# ECE_362_mini_project2.net
KiCad netlist of a schematic drawn in EAGLE
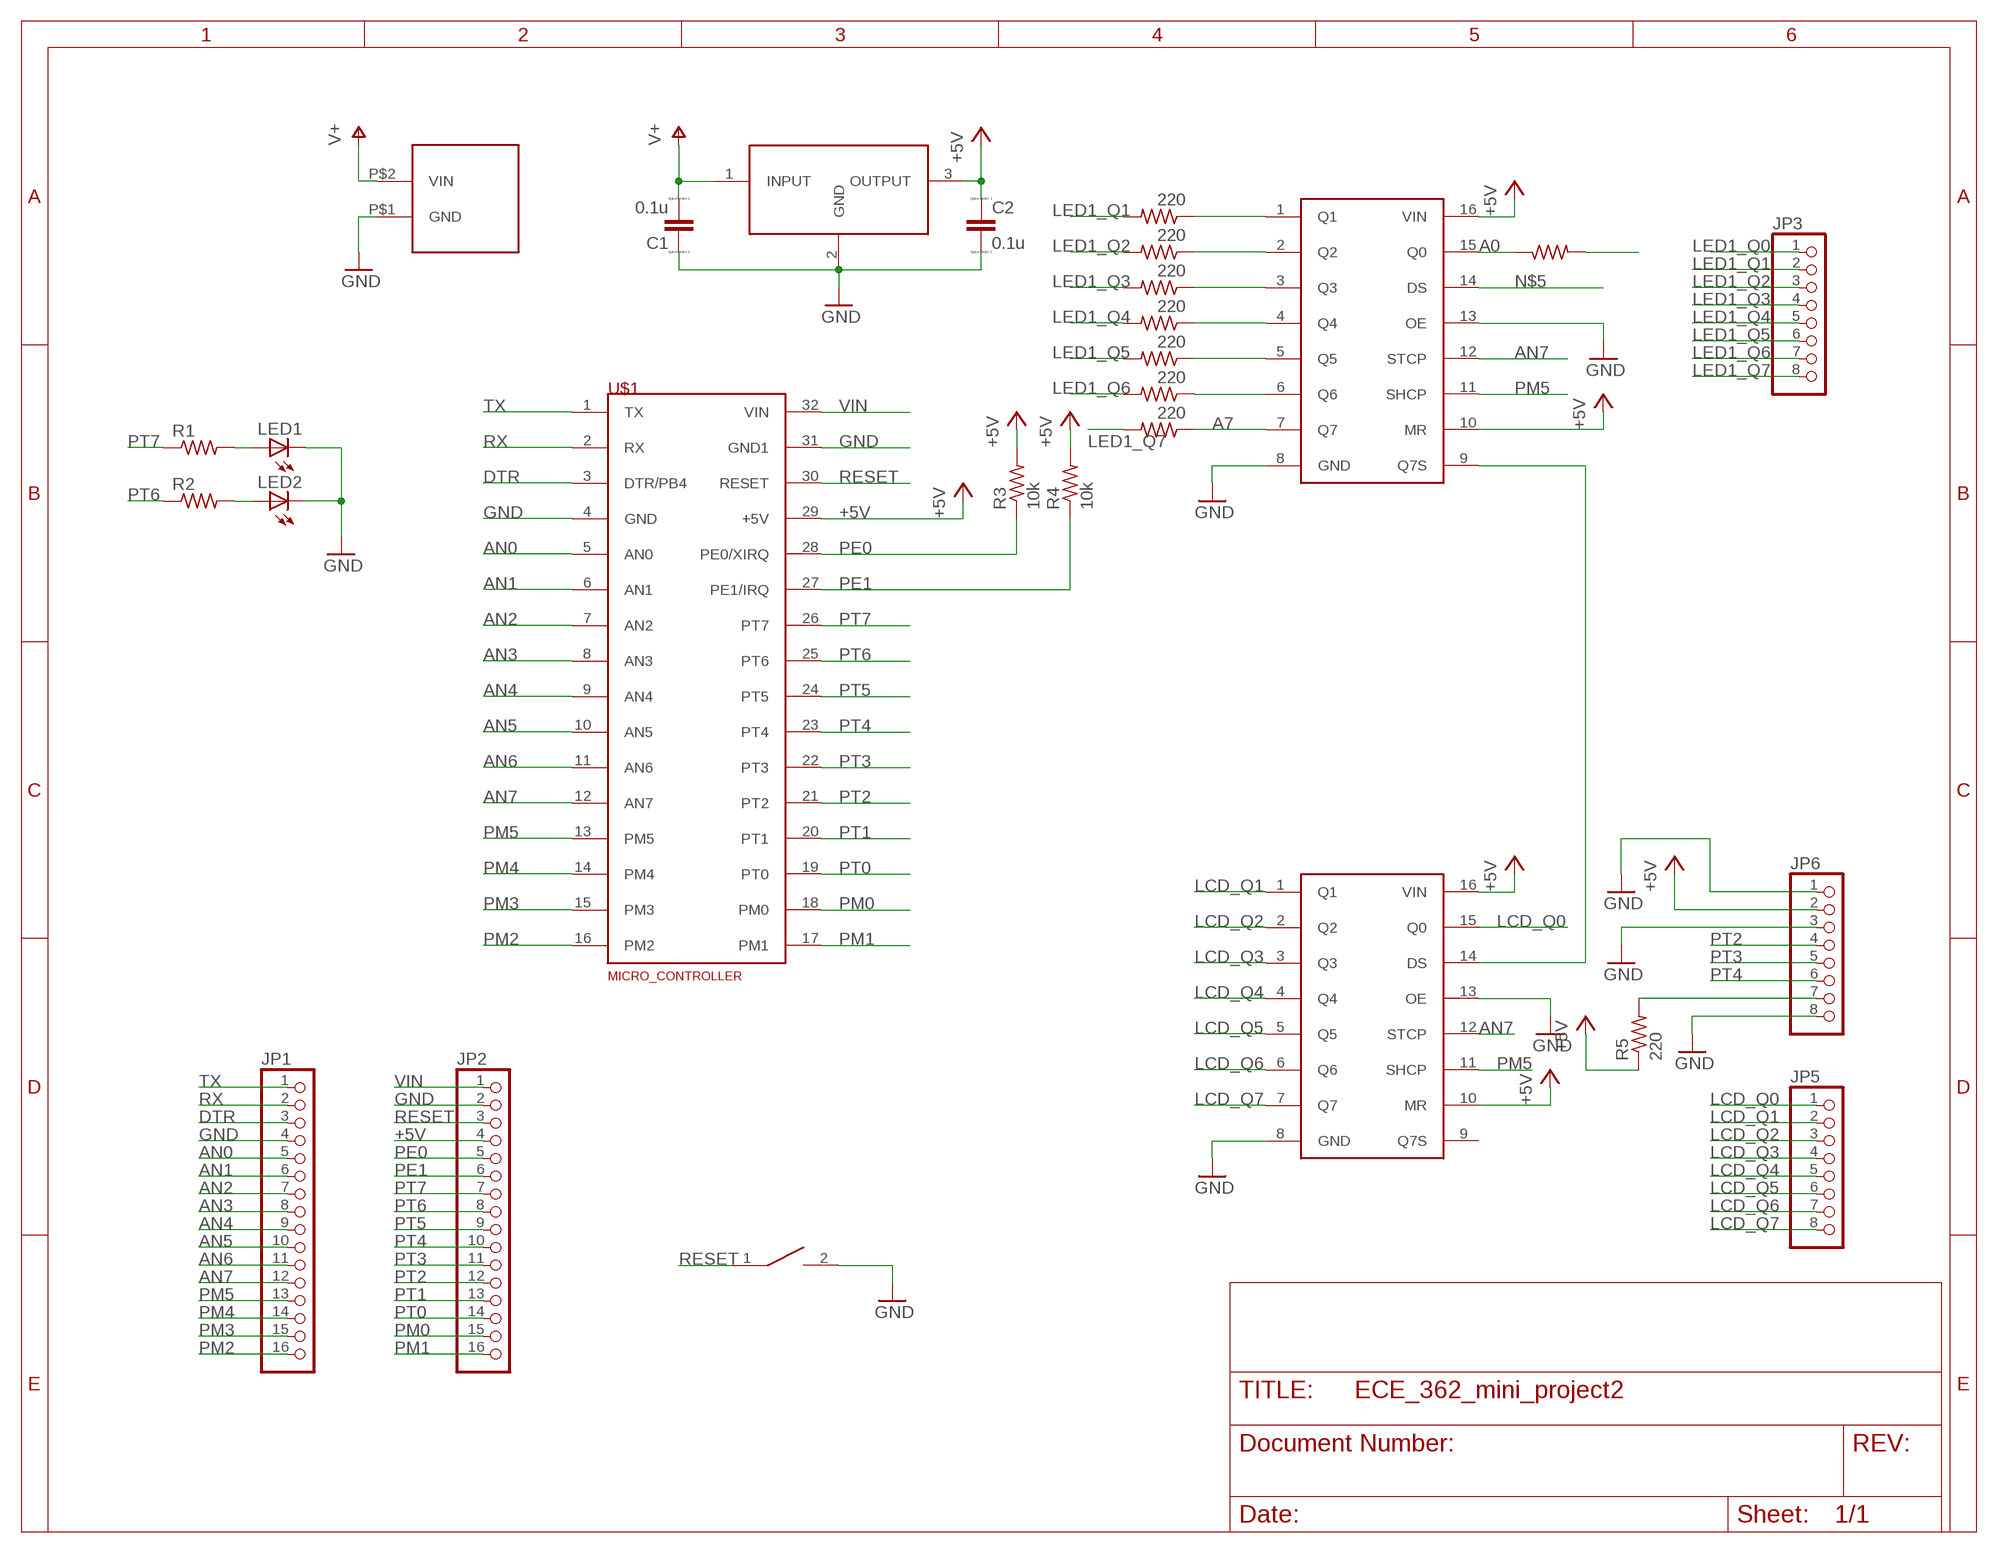
[diagram p0: schematic, sheet 1]

(export (version "E")
  (design (tool "Eeschema 10.0.6"))
  (components
    (comp (ref "BOOT_SW")
      (value "SWITCH")
      (footprint "eagle-import:SW_2512")
      (libsource (lib "eagle-import") (part "SWITCH"))
    )
    (comp (ref "C1")
      (value "0.1u")
      (footprint "eagle-import:C0603")
      (libsource (lib "eagle-import") (part "CC0603"))
    )
    (comp (ref "C2")
      (value "0.1u")
      (footprint "eagle-import:C0603")
      (libsource (lib "eagle-import") (part "CC0603"))
    )
    (comp (ref "JP1")
      (value "PINHD-1X16")
      (footprint "eagle-import:1X16")
      (libsource (lib "eagle-import") (part "PINHD-1X16"))
    )
    (comp (ref "JP2")
      (value "PINHD-1X16")
      (footprint "eagle-import:1X16")
      (libsource (lib "eagle-import") (part "PINHD-1X16"))
    )
    (comp (ref "JP3")
      (value "PINHD-1X8")
      (footprint "eagle-import:1X08")
      (libsource (lib "eagle-import") (part "PINHD-1X8"))
    )
    (comp (ref "JP5")
      (value "PINHD-1X8")
      (footprint "eagle-import:1X08")
      (libsource (lib "eagle-import") (part "PINHD-1X8"))
    )
    (comp (ref "JP6")
      (value "PINHD-1X8")
      (footprint "eagle-import:1X08")
      (libsource (lib "eagle-import") (part "PINHD-1X8"))
    )
    (comp (ref "LED1")
      (value "LEDCHIPLED_0603")
      (footprint "eagle-import:CHIPLED_0603")
      (libsource (lib "eagle-import") (part "LEDCHIPLED_0603"))
    )
    (comp (ref "LED2")
      (value "LEDCHIPLED_0603")
      (footprint "eagle-import:CHIPLED_0603")
      (libsource (lib "eagle-import") (part "LEDCHIPLED_0603"))
    )
    (comp (ref "R1")
      (value "R-US_R0603")
      (footprint "eagle-import:R0603")
      (libsource (lib "eagle-import") (part "R-US_R0603"))
    )
    (comp (ref "R2")
      (value "R-US_R0603")
      (footprint "eagle-import:R0603")
      (libsource (lib "eagle-import") (part "R-US_R0603"))
    )
    (comp (ref "R3")
      (value "10k")
      (footprint "eagle-import:R0603")
      (libsource (lib "eagle-import") (part "R-US_R0603"))
    )
    (comp (ref "R4")
      (value "10k")
      (footprint "eagle-import:R0603")
      (libsource (lib "eagle-import") (part "R-US_R0603"))
    )
    (comp (ref "R5")
      (value "220")
      (footprint "eagle-import:R0603")
      (libsource (lib "eagle-import") (part "R-US_R0603"))
    )
    (comp (ref "R6")
      (value "220")
      (footprint "eagle-import:R0603")
      (libsource (lib "eagle-import") (part "R-US_R0603"))
    )
    (comp (ref "R7")
      (value "220")
      (footprint "eagle-import:R0603")
      (libsource (lib "eagle-import") (part "R-US_R0603"))
    )
    (comp (ref "R8")
      (value "220")
      (footprint "eagle-import:R0603")
      (libsource (lib "eagle-import") (part "R-US_R0603"))
    )
    (comp (ref "R9")
      (value "220")
      (footprint "eagle-import:R0603")
      (libsource (lib "eagle-import") (part "R-US_R0603"))
    )
    (comp (ref "R10")
      (value "220")
      (footprint "eagle-import:R0603")
      (libsource (lib "eagle-import") (part "R-US_R0603"))
    )
    (comp (ref "R11")
      (value "220")
      (footprint "eagle-import:R0603")
      (libsource (lib "eagle-import") (part "R-US_R0603"))
    )
    (comp (ref "R12")
      (value "220")
      (footprint "eagle-import:R0603")
      (libsource (lib "eagle-import") (part "R-US_R0603"))
    )
    (comp (ref "R20")
      (value "220")
      (footprint "eagle-import:R0603")
      (libsource (lib "eagle-import") (part "R-US_R0603"))
    )
    (comp (ref "U$1")
      (value "MICRO_CONTROLLER")
      (footprint "eagle-import:MICRO_CONTROLLER")
      (libsource (lib "eagle-import") (part "MICRO_CONTROLLER"))
    )
    (comp (ref "U$2")
      (value "SHIFT_REGISTER")
      (footprint "eagle-import:N5")
      (libsource (lib "eagle-import") (part "SHIFT_REGISTER"))
    )
    (comp (ref "U$3")
      (value "XT60")
      (footprint "eagle-import:XT60")
      (libsource (lib "eagle-import") (part "XT60"))
    )
    (comp (ref "U$5")
      (value "SHIFT_REGISTER")
      (footprint "eagle-import:N5")
      (libsource (lib "eagle-import") (part "SHIFT_REGISTER"))
    )
    (comp (ref "U$6")
      (value "L7805CV")
      (footprint "eagle-import:L7805CV")
      (libsource (lib "eagle-import") (part "L7805CV"))
    )
  )
  (nets
    (net (code "1") (name "+5V") (class "Default")
      (node (ref "C2") (pin "1") (pinfunction "1_1") (pintype "passive"))
      (node (ref "JP2") (pin "4") (pinfunction "4_4") (pintype "passive"))
      (node (ref "JP6") (pin "2") (pinfunction "2_2") (pintype "passive"))
      (node (ref "R3") (pin "2") (pinfunction "2_2") (pintype "passive"))
      (node (ref "R4") (pin "2") (pinfunction "2_2") (pintype "passive"))
      (node (ref "R5") (pin "1") (pinfunction "1_1") (pintype "passive"))
      (node (ref "U$1") (pin "29") (pinfunction "+5V_29") (pintype "bidirectional"))
      (node (ref "U$2") (pin "10") (pinfunction "MR_10") (pintype "bidirectional"))
      (node (ref "U$2") (pin "16") (pinfunction "VIN_16") (pintype "bidirectional"))
      (node (ref "U$5") (pin "10") (pinfunction "MR_10") (pintype "bidirectional"))
      (node (ref "U$5") (pin "16") (pinfunction "VIN_16") (pintype "bidirectional"))
      (node (ref "U$6") (pin "3") (pinfunction "OUTPUT_3") (pintype "bidirectional"))
    )
    (net (code "2") (name "/A0") (class "Default")
      (node (ref "R20") (pin "1") (pinfunction "1_1") (pintype "passive"))
      (node (ref "U$2") (pin "15") (pinfunction "Q0_15") (pintype "bidirectional"))
    )
    (net (code "3") (name "/A7") (class "Default")
      (node (ref "R12") (pin "1") (pinfunction "1_1") (pintype "passive"))
      (node (ref "U$2") (pin "7") (pinfunction "Q7_7") (pintype "bidirectional"))
    )
    (net (code "4") (name "/AN0") (class "Default")
      (node (ref "JP1") (pin "5") (pinfunction "5_5") (pintype "passive"))
      (node (ref "U$1") (pin "5") (pinfunction "AN0_5") (pintype "bidirectional"))
    )
    (net (code "5") (name "/AN1") (class "Default")
      (node (ref "JP1") (pin "6") (pinfunction "6_6") (pintype "passive"))
      (node (ref "U$1") (pin "6") (pinfunction "AN1_6") (pintype "bidirectional"))
    )
    (net (code "6") (name "/AN2") (class "Default")
      (node (ref "JP1") (pin "7") (pinfunction "7_7") (pintype "passive"))
      (node (ref "U$1") (pin "7") (pinfunction "AN2_7") (pintype "bidirectional"))
    )
    (net (code "7") (name "/AN3") (class "Default")
      (node (ref "JP1") (pin "8") (pinfunction "8_8") (pintype "passive"))
      (node (ref "U$1") (pin "8") (pinfunction "AN3_8") (pintype "bidirectional"))
    )
    (net (code "8") (name "/AN4") (class "Default")
      (node (ref "JP1") (pin "9") (pinfunction "9_9") (pintype "passive"))
      (node (ref "U$1") (pin "9") (pinfunction "AN4_9") (pintype "bidirectional"))
    )
    (net (code "9") (name "/AN5") (class "Default")
      (node (ref "JP1") (pin "10") (pinfunction "10_10") (pintype "passive"))
      (node (ref "U$1") (pin "10") (pinfunction "AN5_10") (pintype "bidirectional"))
    )
    (net (code "10") (name "/AN6") (class "Default")
      (node (ref "JP1") (pin "11") (pinfunction "11_11") (pintype "passive"))
      (node (ref "U$1") (pin "11") (pinfunction "AN6_11") (pintype "bidirectional"))
    )
    (net (code "11") (name "/AN7") (class "Default")
      (node (ref "JP1") (pin "12") (pinfunction "12_12") (pintype "passive"))
      (node (ref "U$1") (pin "12") (pinfunction "AN7_12") (pintype "bidirectional"))
      (node (ref "U$2") (pin "12") (pinfunction "STCP_12") (pintype "bidirectional"))
      (node (ref "U$5") (pin "12") (pinfunction "STCP_12") (pintype "bidirectional"))
    )
    (net (code "12") (name "/DTR") (class "Default")
      (node (ref "JP1") (pin "3") (pinfunction "3_3") (pintype "passive"))
      (node (ref "U$1") (pin "3") (pinfunction "DTR/PB4_3") (pintype "bidirectional"))
    )
    (net (code "13") (name "/LCD_Q0") (class "Default")
      (node (ref "JP5") (pin "1") (pinfunction "1_1") (pintype "passive"))
      (node (ref "U$5") (pin "15") (pinfunction "Q0_15") (pintype "bidirectional"))
    )
    (net (code "14") (name "/LCD_Q1") (class "Default")
      (node (ref "JP5") (pin "2") (pinfunction "2_2") (pintype "passive"))
      (node (ref "U$5") (pin "1") (pinfunction "Q1_1") (pintype "bidirectional"))
    )
    (net (code "15") (name "/LCD_Q2") (class "Default")
      (node (ref "JP5") (pin "3") (pinfunction "3_3") (pintype "passive"))
      (node (ref "U$5") (pin "2") (pinfunction "Q2_2") (pintype "bidirectional"))
    )
    (net (code "16") (name "/LCD_Q3") (class "Default")
      (node (ref "JP5") (pin "4") (pinfunction "4_4") (pintype "passive"))
      (node (ref "U$5") (pin "3") (pinfunction "Q3_3") (pintype "bidirectional"))
    )
    (net (code "17") (name "/LCD_Q4") (class "Default")
      (node (ref "JP5") (pin "5") (pinfunction "5_5") (pintype "passive"))
      (node (ref "U$5") (pin "4") (pinfunction "Q4_4") (pintype "bidirectional"))
    )
    (net (code "18") (name "/LCD_Q5") (class "Default")
      (node (ref "JP5") (pin "6") (pinfunction "6_6") (pintype "passive"))
      (node (ref "U$5") (pin "5") (pinfunction "Q5_5") (pintype "bidirectional"))
    )
    (net (code "19") (name "/LCD_Q6") (class "Default")
      (node (ref "JP5") (pin "7") (pinfunction "7_7") (pintype "passive"))
      (node (ref "U$5") (pin "6") (pinfunction "Q6_6") (pintype "bidirectional"))
    )
    (net (code "20") (name "/LCD_Q7") (class "Default")
      (node (ref "JP5") (pin "8") (pinfunction "8_8") (pintype "passive"))
      (node (ref "U$5") (pin "7") (pinfunction "Q7_7") (pintype "bidirectional"))
    )
    (net (code "21") (name "/LED1_Q0") (class "Default")
      (node (ref "JP3") (pin "1") (pinfunction "1_1") (pintype "passive"))
      (node (ref "R20") (pin "2") (pinfunction "2_2") (pintype "passive"))
    )
    (net (code "22") (name "/LED1_Q1") (class "Default")
      (node (ref "JP3") (pin "2") (pinfunction "2_2") (pintype "passive"))
      (node (ref "R6") (pin "2") (pinfunction "2_2") (pintype "passive"))
    )
    (net (code "23") (name "/LED1_Q2") (class "Default")
      (node (ref "JP3") (pin "3") (pinfunction "3_3") (pintype "passive"))
      (node (ref "R7") (pin "2") (pinfunction "2_2") (pintype "passive"))
    )
    (net (code "24") (name "/LED1_Q3") (class "Default")
      (node (ref "JP3") (pin "4") (pinfunction "4_4") (pintype "passive"))
      (node (ref "R8") (pin "2") (pinfunction "2_2") (pintype "passive"))
    )
    (net (code "25") (name "/LED1_Q4") (class "Default")
      (node (ref "JP3") (pin "5") (pinfunction "5_5") (pintype "passive"))
      (node (ref "R9") (pin "2") (pinfunction "2_2") (pintype "passive"))
    )
    (net (code "26") (name "/LED1_Q5") (class "Default")
      (node (ref "JP3") (pin "6") (pinfunction "6_6") (pintype "passive"))
      (node (ref "R10") (pin "2") (pinfunction "2_2") (pintype "passive"))
    )
    (net (code "27") (name "/LED1_Q6") (class "Default")
      (node (ref "JP3") (pin "7") (pinfunction "7_7") (pintype "passive"))
      (node (ref "R11") (pin "2") (pinfunction "2_2") (pintype "passive"))
    )
    (net (code "28") (name "/LED1_Q7") (class "Default")
      (node (ref "JP3") (pin "8") (pinfunction "8_8") (pintype "passive"))
      (node (ref "R12") (pin "2") (pinfunction "2_2") (pintype "passive"))
    )
    (net (code "29") (name "/N$5") (class "Default")
      (node (ref "U$2") (pin "14") (pinfunction "DS_14") (pintype "bidirectional"))
    )
    (net (code "30") (name "/PE0") (class "Default")
      (node (ref "JP2") (pin "5") (pinfunction "5_5") (pintype "passive"))
      (node (ref "R3") (pin "1") (pinfunction "1_1") (pintype "passive"))
      (node (ref "U$1") (pin "28") (pinfunction "PE0/XIRQ_28") (pintype "bidirectional"))
    )
    (net (code "31") (name "/PE1") (class "Default")
      (node (ref "JP2") (pin "6") (pinfunction "6_6") (pintype "passive"))
      (node (ref "R4") (pin "1") (pinfunction "1_1") (pintype "passive"))
      (node (ref "U$1") (pin "27") (pinfunction "PE1/IRQ_27") (pintype "bidirectional"))
    )
    (net (code "32") (name "/PM0") (class "Default")
      (node (ref "JP2") (pin "15") (pinfunction "15_15") (pintype "passive"))
      (node (ref "U$1") (pin "18") (pinfunction "PM0_18") (pintype "bidirectional"))
    )
    (net (code "33") (name "/PM1") (class "Default")
      (node (ref "JP2") (pin "16") (pinfunction "16_16") (pintype "passive"))
      (node (ref "U$1") (pin "17") (pinfunction "PM1_17") (pintype "bidirectional"))
    )
    (net (code "34") (name "/PM2") (class "Default")
      (node (ref "JP1") (pin "16") (pinfunction "16_16") (pintype "passive"))
      (node (ref "U$1") (pin "16") (pinfunction "PM2_16") (pintype "bidirectional"))
    )
    (net (code "35") (name "/PM3") (class "Default")
      (node (ref "JP1") (pin "15") (pinfunction "15_15") (pintype "passive"))
      (node (ref "U$1") (pin "15") (pinfunction "PM3_15") (pintype "bidirectional"))
    )
    (net (code "36") (name "/PM4") (class "Default")
      (node (ref "JP1") (pin "14") (pinfunction "14_14") (pintype "passive"))
      (node (ref "U$1") (pin "14") (pinfunction "PM4_14") (pintype "bidirectional"))
    )
    (net (code "37") (name "/PM5") (class "Default")
      (node (ref "JP1") (pin "13") (pinfunction "13_13") (pintype "passive"))
      (node (ref "U$1") (pin "13") (pinfunction "PM5_13") (pintype "bidirectional"))
      (node (ref "U$2") (pin "11") (pinfunction "SHCP_11") (pintype "bidirectional"))
      (node (ref "U$5") (pin "11") (pinfunction "SHCP_11") (pintype "bidirectional"))
    )
    (net (code "38") (name "/PT0") (class "Default")
      (node (ref "JP2") (pin "14") (pinfunction "14_14") (pintype "passive"))
      (node (ref "U$1") (pin "19") (pinfunction "PT0_19") (pintype "bidirectional"))
    )
    (net (code "39") (name "/PT1") (class "Default")
      (node (ref "JP2") (pin "13") (pinfunction "13_13") (pintype "passive"))
      (node (ref "U$1") (pin "20") (pinfunction "PT1_20") (pintype "bidirectional"))
    )
    (net (code "40") (name "/PT2") (class "Default")
      (node (ref "JP2") (pin "12") (pinfunction "12_12") (pintype "passive"))
      (node (ref "JP6") (pin "4") (pinfunction "4_4") (pintype "passive"))
      (node (ref "U$1") (pin "21") (pinfunction "PT2_21") (pintype "bidirectional"))
    )
    (net (code "41") (name "/PT3") (class "Default")
      (node (ref "JP2") (pin "11") (pinfunction "11_11") (pintype "passive"))
      (node (ref "JP6") (pin "5") (pinfunction "5_5") (pintype "passive"))
      (node (ref "U$1") (pin "22") (pinfunction "PT3_22") (pintype "bidirectional"))
    )
    (net (code "42") (name "/PT4") (class "Default")
      (node (ref "JP2") (pin "10") (pinfunction "10_10") (pintype "passive"))
      (node (ref "JP6") (pin "6") (pinfunction "6_6") (pintype "passive"))
      (node (ref "U$1") (pin "23") (pinfunction "PT4_23") (pintype "bidirectional"))
    )
    (net (code "43") (name "/PT5") (class "Default")
      (node (ref "JP2") (pin "9") (pinfunction "9_9") (pintype "passive"))
      (node (ref "U$1") (pin "24") (pinfunction "PT5_24") (pintype "bidirectional"))
    )
    (net (code "44") (name "/PT6") (class "Default")
      (node (ref "JP2") (pin "8") (pinfunction "8_8") (pintype "passive"))
      (node (ref "R2") (pin "1") (pinfunction "1_1") (pintype "passive"))
      (node (ref "U$1") (pin "25") (pinfunction "PT6_25") (pintype "bidirectional"))
    )
    (net (code "45") (name "/PT7") (class "Default")
      (node (ref "JP2") (pin "7") (pinfunction "7_7") (pintype "passive"))
      (node (ref "R1") (pin "1") (pinfunction "1_1") (pintype "passive"))
      (node (ref "U$1") (pin "26") (pinfunction "PT7_26") (pintype "bidirectional"))
    )
    (net (code "46") (name "/RESET") (class "Default")
      (node (ref "BOOT_SW") (pin "1") (pinfunction "P$1_1") (pintype "bidirectional"))
      (node (ref "JP2") (pin "3") (pinfunction "3_3") (pintype "passive"))
      (node (ref "U$1") (pin "30") (pinfunction "RESET_30") (pintype "bidirectional"))
    )
    (net (code "47") (name "/RX") (class "Default")
      (node (ref "JP1") (pin "2") (pinfunction "2_2") (pintype "passive"))
      (node (ref "U$1") (pin "2") (pinfunction "RX_2") (pintype "bidirectional"))
    )
    (net (code "48") (name "/TX") (class "Default")
      (node (ref "JP1") (pin "1") (pinfunction "1_1") (pintype "passive"))
      (node (ref "U$1") (pin "1") (pinfunction "TX_1") (pintype "bidirectional"))
    )
    (net (code "49") (name "/VIN") (class "Default")
      (node (ref "JP2") (pin "1") (pinfunction "1_1") (pintype "passive"))
      (node (ref "U$1") (pin "32") (pinfunction "VIN_32") (pintype "bidirectional"))
    )
    (net (code "50") (name "GND") (class "Default")
      (node (ref "BOOT_SW") (pin "2") (pinfunction "P$2_2") (pintype "bidirectional"))
      (node (ref "C1") (pin "1") (pinfunction "1_1") (pintype "passive"))
      (node (ref "C2") (pin "2") (pinfunction "2_2") (pintype "passive"))
      (node (ref "JP1") (pin "4") (pinfunction "4_4") (pintype "passive"))
      (node (ref "JP2") (pin "2") (pinfunction "2_2") (pintype "passive"))
      (node (ref "JP6") (pin "1") (pinfunction "1_1") (pintype "passive"))
      (node (ref "JP6") (pin "3") (pinfunction "3_3") (pintype "passive"))
      (node (ref "JP6") (pin "8") (pinfunction "8_8") (pintype "passive"))
      (node (ref "LED1") (pin "C") (pinfunction "C_C") (pintype "passive"))
      (node (ref "LED2") (pin "C") (pinfunction "C_C") (pintype "passive"))
      (node (ref "U$1") (pin "31") (pinfunction "GND1_31") (pintype "bidirectional"))
      (node (ref "U$1") (pin "4") (pinfunction "GND_4") (pintype "bidirectional"))
      (node (ref "U$2") (pin "13") (pinfunction "OE_13") (pintype "bidirectional"))
      (node (ref "U$2") (pin "8") (pinfunction "GND_8") (pintype "bidirectional"))
      (node (ref "U$3") (pin "P$1") (pinfunction "GND_P$1") (pintype "bidirectional"))
      (node (ref "U$5") (pin "13") (pinfunction "OE_13") (pintype "bidirectional"))
      (node (ref "U$5") (pin "8") (pinfunction "GND_8") (pintype "bidirectional"))
      (node (ref "U$6") (pin "2") (pinfunction "GND_2") (pintype "bidirectional"))
    )
    (net (code "51") (name "Net-(JP6-Pad7)") (class "Default")
      (node (ref "JP6") (pin "7") (pinfunction "7_7") (pintype "passive"))
      (node (ref "R5") (pin "2") (pinfunction "2_2") (pintype "passive"))
    )
    (net (code "52") (name "Net-(LED1-PadA)") (class "Default")
      (node (ref "LED1") (pin "A") (pinfunction "A_A") (pintype "passive"))
      (node (ref "R1") (pin "2") (pinfunction "2_2") (pintype "passive"))
    )
    (net (code "53") (name "Net-(LED2-PadA)") (class "Default")
      (node (ref "LED2") (pin "A") (pinfunction "A_A") (pintype "passive"))
      (node (ref "R2") (pin "2") (pinfunction "2_2") (pintype "passive"))
    )
    (net (code "54") (name "Net-(U$2-Q1)") (class "Default")
      (node (ref "R6") (pin "1") (pinfunction "1_1") (pintype "passive"))
      (node (ref "U$2") (pin "1") (pinfunction "Q1_1") (pintype "bidirectional"))
    )
    (net (code "55") (name "Net-(U$2-Q2)") (class "Default")
      (node (ref "R7") (pin "1") (pinfunction "1_1") (pintype "passive"))
      (node (ref "U$2") (pin "2") (pinfunction "Q2_2") (pintype "bidirectional"))
    )
    (net (code "56") (name "Net-(U$2-Q3)") (class "Default")
      (node (ref "R8") (pin "1") (pinfunction "1_1") (pintype "passive"))
      (node (ref "U$2") (pin "3") (pinfunction "Q3_3") (pintype "bidirectional"))
    )
    (net (code "57") (name "Net-(U$2-Q4)") (class "Default")
      (node (ref "R9") (pin "1") (pinfunction "1_1") (pintype "passive"))
      (node (ref "U$2") (pin "4") (pinfunction "Q4_4") (pintype "bidirectional"))
    )
    (net (code "58") (name "Net-(U$2-Q5)") (class "Default")
      (node (ref "R10") (pin "1") (pinfunction "1_1") (pintype "passive"))
      (node (ref "U$2") (pin "5") (pinfunction "Q5_5") (pintype "bidirectional"))
    )
    (net (code "59") (name "Net-(U$2-Q6)") (class "Default")
      (node (ref "R11") (pin "1") (pinfunction "1_1") (pintype "passive"))
      (node (ref "U$2") (pin "6") (pinfunction "Q6_6") (pintype "bidirectional"))
    )
    (net (code "60") (name "Net-(U$2-Q7S)") (class "Default")
      (node (ref "U$2") (pin "9") (pinfunction "Q7S_9") (pintype "bidirectional"))
      (node (ref "U$5") (pin "14") (pinfunction "DS_14") (pintype "bidirectional"))
    )
    (net (code "61") (name "V+") (class "Default")
      (node (ref "C1") (pin "2") (pinfunction "2_2") (pintype "passive"))
      (node (ref "U$3") (pin "P$2") (pinfunction "VIN_P$2") (pintype "bidirectional"))
      (node (ref "U$6") (pin "1") (pinfunction "INPUT_1") (pintype "bidirectional"))
    )
    (net (code "62") (name "unconnected-(U$5-Q7S-Pad9)") (class "Default")
      (node (ref "U$5") (pin "9") (pinfunction "Q7S_9") (pintype "bidirectional"))
    )
  )
)
